# 50mil_5x2_JTAG_to_100mil_5x2_v20.net
KiCad netlist of a schematic drawn in EAGLE
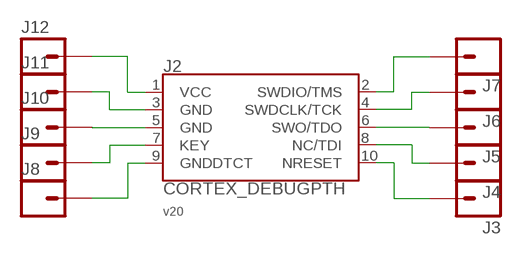
[diagram p0: schematic, sheet 1]

(export (version "E")
  (design (tool "Eeschema 10.0.6"))
  (components
    (comp (ref "J2")
      (value "CORTEX_DEBUGPTH")
      (footprint "eagle-import:2X5-PTH-1.27MM")
      (libsource (lib "eagle-import") (part "CORTEX_DEBUGPTH"))
    )
    (comp (ref "J3")
      (value "M01OFFSET")
      (footprint "eagle-import:1X01_OFFSET")
      (libsource (lib "eagle-import") (part "M01OFFSET"))
    )
    (comp (ref "J4")
      (value "M01OFFSET")
      (footprint "eagle-import:1X01_OFFSET")
      (libsource (lib "eagle-import") (part "M01OFFSET"))
    )
    (comp (ref "J5")
      (value "M01OFFSET")
      (footprint "eagle-import:1X01_OFFSET")
      (libsource (lib "eagle-import") (part "M01OFFSET"))
    )
    (comp (ref "J6")
      (value "M01OFFSET")
      (footprint "eagle-import:1X01_OFFSET")
      (libsource (lib "eagle-import") (part "M01OFFSET"))
    )
    (comp (ref "J7")
      (value "M01OFFSET")
      (footprint "eagle-import:1X01_OFFSET")
      (libsource (lib "eagle-import") (part "M01OFFSET"))
    )
    (comp (ref "J8")
      (value "M01OFFSET")
      (footprint "eagle-import:1X01_OFFSET")
      (libsource (lib "eagle-import") (part "M01OFFSET"))
    )
    (comp (ref "J9")
      (value "M01OFFSET")
      (footprint "eagle-import:1X01_OFFSET")
      (libsource (lib "eagle-import") (part "M01OFFSET"))
    )
    (comp (ref "J10")
      (value "M01OFFSET")
      (footprint "eagle-import:1X01_OFFSET")
      (libsource (lib "eagle-import") (part "M01OFFSET"))
    )
    (comp (ref "J11")
      (value "M01OFFSET")
      (footprint "eagle-import:1X01_OFFSET")
      (libsource (lib "eagle-import") (part "M01OFFSET"))
    )
    (comp (ref "J12")
      (value "M01OFFSET")
      (footprint "eagle-import:1X01_OFFSET")
      (libsource (lib "eagle-import") (part "M01OFFSET"))
    )
  )
  (nets
    (net (code "1") (name "Net-(J2-GNDDTCT)") (class "Default")
      (node (ref "J2") (pin "9") (pinfunction "GNDDTCT_9") (pintype "bidirectional"))
      (node (ref "J8") (pin "1") (pinfunction "1_1") (pintype "passive"))
    )
    (net (code "2") (name "Net-(J2-KEY)") (class "Default")
      (node (ref "J2") (pin "7") (pinfunction "KEY_7") (pintype "bidirectional"))
      (node (ref "J9") (pin "1") (pinfunction "1_1") (pintype "passive"))
    )
    (net (code "3") (name "Net-(J2-NC{slash}TDI)") (class "Default")
      (node (ref "J2") (pin "8") (pinfunction "NC/TDI_8") (pintype "bidirectional"))
      (node (ref "J4") (pin "1") (pinfunction "1_1") (pintype "passive"))
    )
    (net (code "4") (name "Net-(J2-NRESET)") (class "Default")
      (node (ref "J2") (pin "10") (pinfunction "NRESET_10") (pintype "bidirectional"))
      (node (ref "J3") (pin "1") (pinfunction "1_1") (pintype "passive"))
    )
    (net (code "5") (name "Net-(J2-SWDCLK{slash}TCK)") (class "Default")
      (node (ref "J2") (pin "4") (pinfunction "SWDCLK/TCK_4") (pintype "bidirectional"))
      (node (ref "J6") (pin "1") (pinfunction "1_1") (pintype "passive"))
    )
    (net (code "6") (name "Net-(J2-SWDIO{slash}TMS)") (class "Default")
      (node (ref "J2") (pin "2") (pinfunction "SWDIO/TMS_2") (pintype "bidirectional"))
      (node (ref "J7") (pin "1") (pinfunction "1_1") (pintype "passive"))
    )
    (net (code "7") (name "Net-(J2-SWO{slash}TDO)") (class "Default")
      (node (ref "J2") (pin "6") (pinfunction "SWO/TDO_6") (pintype "bidirectional"))
      (node (ref "J5") (pin "1") (pinfunction "1_1") (pintype "passive"))
    )
    (net (code "8") (name "Net-(J2-VCC)") (class "Default")
      (node (ref "J12") (pin "1") (pinfunction "1_1") (pintype "passive"))
      (node (ref "J2") (pin "1") (pinfunction "VCC_1") (pintype "bidirectional"))
    )
    (net (code "9") (name "Net-(J10-Pad1)") (class "Default")
      (node (ref "J10") (pin "1") (pinfunction "1_1") (pintype "passive"))
      (node (ref "J2") (pin "5") (pinfunction "GND_5") (pintype "bidirectional"))
    )
    (net (code "10") (name "Net-(J11-Pad1)") (class "Default")
      (node (ref "J11") (pin "1") (pinfunction "1_1") (pintype "passive"))
      (node (ref "J2") (pin "3") (pinfunction "GND_3") (pintype "bidirectional"))
    )
  )
)
